# MCU.net
KiCad netlist of a schematic drawn in Altium Designer
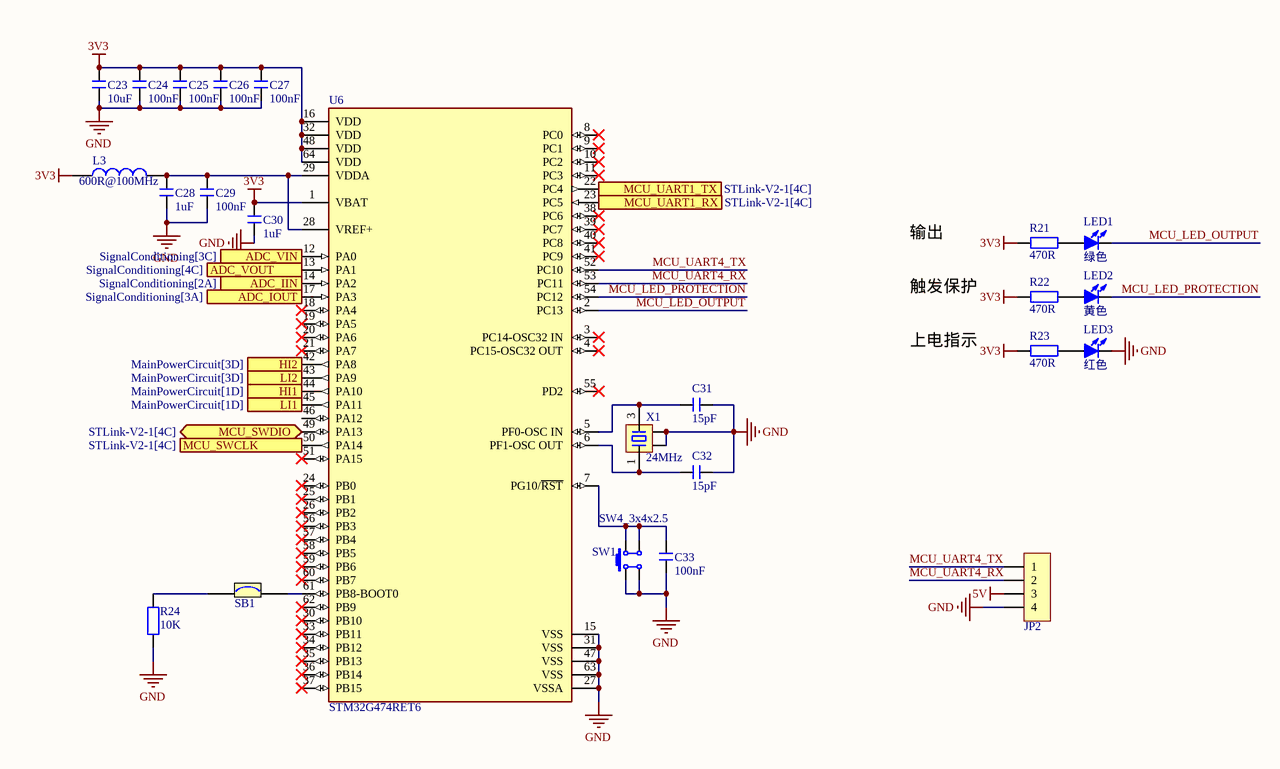
[diagram p0: MCU.SchDoc]

(export (version "E")
  (design (tool "Eeschema 10.0.6"))
  (components
    (comp (ref "C23")
      (value "10uF")
      (footprint "C 0402_L")
      (description "无极性贴片电容")
      (fields (field (name "版权归属") "源创客"))
      (libsource (lib "源创客") (part "C"))
    )
    (comp (ref "C24")
      (value "100nF")
      (footprint "C 0402_L")
      (description "无极性贴片电容")
      (fields (field (name "版权归属") "源创客"))
      (libsource (lib "源创客") (part "C"))
    )
    (comp (ref "C25")
      (value "100nF")
      (footprint "C 0402_L")
      (description "无极性贴片电容")
      (fields (field (name "版权归属") "源创客"))
      (libsource (lib "源创客") (part "C"))
    )
    (comp (ref "C26")
      (value "100nF")
      (footprint "C 0402_L")
      (description "无极性贴片电容")
      (fields (field (name "版权归属") "源创客"))
      (libsource (lib "源创客") (part "C"))
    )
    (comp (ref "C27")
      (value "100nF")
      (footprint "C 0402_L")
      (description "无极性贴片电容")
      (fields (field (name "版权归属") "源创客"))
      (libsource (lib "源创客") (part "C"))
    )
    (comp (ref "C28")
      (value "1uF")
      (footprint "C 0402_L")
      (description "无极性贴片电容")
      (fields (field (name "版权归属") "源创客"))
      (libsource (lib "源创客") (part "C"))
    )
    (comp (ref "C29")
      (value "100nF")
      (footprint "C 0402_L")
      (description "无极性贴片电容")
      (fields (field (name "版权归属") "源创客"))
      (libsource (lib "源创客") (part "C"))
    )
    (comp (ref "C30")
      (value "1uF")
      (footprint "C 0402_L")
      (description "无极性贴片电容")
      (fields (field (name "版权归属") "源创客"))
      (libsource (lib "源创客") (part "C"))
    )
    (comp (ref "C31")
      (value "15pF")
      (footprint "C 0402_L")
      (description "无极性贴片电容")
      (fields (field (name "版权归属") "源创客"))
      (libsource (lib "源创客") (part "C"))
    )
    (comp (ref "C32")
      (value "15pF")
      (footprint "C 0402_L")
      (description "无极性贴片电容")
      (fields (field (name "版权归属") "源创客"))
      (libsource (lib "源创客") (part "C"))
    )
    (comp (ref "C33")
      (value "100nF")
      (footprint "C 0402_L")
      (description "无极性贴片电容")
      (fields (field (name "版权归属") "源创客"))
      (libsource (lib "源创客") (part "C"))
    )
    (comp (ref "JP2")
      (value "HDR-1X4")
      (footprint "XH2.54-WI-4P")
      (description "4P接插件")
      (libsource (lib "5.5 - 2.54mm(100mil)连接器(XH2.54)") (part "Header 4"))
    )
    (comp (ref "L3")
      (value "600R@100MHz")
      (footprint "L 0603")
      (description "小功率贴片电感")
      (fields (field (name "版权归属") "源创客"))
      (libsource (lib "源创客") (part "L"))
    )
    (comp (ref "LED1")
      (value "绿色")
      (footprint "LED 0603G")
      (description "贴片LED")
      (fields (field (name "版权归属") "源创客"))
      (libsource (lib "源创客") (part "LED-SMD"))
    )
    (comp (ref "LED2")
      (value "黄色")
      (footprint "LED 0603Y")
      (description "贴片LED")
      (fields (field (name "版权归属") "源创客"))
      (libsource (lib "源创客") (part "LED-SMD"))
    )
    (comp (ref "LED3")
      (value "红色")
      (footprint "LED 0603R")
      (description "贴片LED")
      (fields (field (name "版权归属") "源创客"))
      (libsource (lib "源创客") (part "LED-SMD"))
    )
    (comp (ref "R21")
      (value "470R")
      (footprint "R 0402_L")
      (description "贴片电阻")
      (fields (field (name "版权归属") "源创客"))
      (libsource (lib "源创客") (part "R"))
    )
    (comp (ref "R22")
      (value "470R")
      (footprint "R 0402_L")
      (description "贴片电阻")
      (fields (field (name "版权归属") "源创客"))
      (libsource (lib "源创客") (part "R"))
    )
    (comp (ref "R23")
      (value "470R")
      (footprint "R 0402_L")
      (description "贴片电阻")
      (fields (field (name "版权归属") "源创客"))
      (libsource (lib "源创客") (part "R"))
    )
    (comp (ref "R24")
      (value "10K")
      (footprint "R 0402_L")
      (description "贴片电阻")
      (fields (field (name "版权归属") "源创客"))
      (libsource (lib "源创客") (part "R"))
    )
    (comp (ref "SB1")
      (value "SelectBit")
      (footprint "SelectBit 0402")
      (description "跨接桥，用于选择不同的模式，可以用锡连上，或者焊上0R电阻")
      (libsource (lib "Display") (part "SelectBit"))
    )
    (comp (ref "SW1")
      (value "SW4_3x4x2.5")
      (footprint "SW4_3x4x2.5")
      (libsource (lib "DigitalBuckBoost") (part "SW4_3x4x2.5"))
    )
    (comp (ref "U6")
      (value "STM32G474RET6")
      (footprint "FP-LQFP64-5W-MFG")
      (description "MAINSTREAM ARM CORTEX-M4 CORE WI")
      (fields
        (field (name "MANUFACTURER") "STMicroelectronics")
        (field (name "OCTOPART") "https://octopart.com/stm32g474ret6-stmicroelectronics-102308483")
      )
      (libsource (lib "Altium Content Vault") (part "f7e4c2ab6713028e27effac94efeea5"))
    )
    (comp (ref "X1")
      (value "24MHz")
      (footprint "XTAL-3225-4P")
      (description "4脚无源晶振(谐振器）")
      (libsource (lib "0.1 - 电阻-电容-电感-晶振-晶体-磁珠-电位器") (part "XTAL-4P"))
    )
  )
  (nets
    (net (code "1") (name "/ADC_IIN") (class "Default")
      (node (ref "U6") (pin "14") (pinfunction "PA2_14") (pintype "input"))
    )
    (net (code "2") (name "/ADC_IOUT") (class "Default")
      (node (ref "U6") (pin "17") (pinfunction "PA3_17") (pintype "input"))
    )
    (net (code "3") (name "/ADC_VIN") (class "Default")
      (node (ref "U6") (pin "12") (pinfunction "PA0_12") (pintype "input"))
    )
    (net (code "4") (name "/ADC_VOUT") (class "Default")
      (node (ref "U6") (pin "13") (pinfunction "PA1_13") (pintype "input"))
    )
    (net (code "5") (name "/HI1") (class "Default")
      (node (ref "U6") (pin "44") (pinfunction "PA10_44") (pintype "output"))
    )
    (net (code "6") (name "/HI2") (class "Default")
      (node (ref "U6") (pin "42") (pinfunction "PA8_42") (pintype "output"))
    )
    (net (code "7") (name "/LI1") (class "Default")
      (node (ref "U6") (pin "45") (pinfunction "PA11_45") (pintype "output"))
    )
    (net (code "8") (name "/LI2") (class "Default")
      (node (ref "U6") (pin "43") (pinfunction "PA9_43") (pintype "output"))
    )
    (net (code "9") (name "/MCU_LED_OUTPUT") (class "Default")
      (node (ref "LED1") (pin "2") (pinfunction "K_2") (pintype "passive"))
      (node (ref "U6") (pin "2") (pinfunction "PC13_2") (pintype "bidirectional"))
    )
    (net (code "10") (name "/MCU_LED_PROTECTION") (class "Default")
      (node (ref "LED2") (pin "2") (pinfunction "K_2") (pintype "passive"))
      (node (ref "U6") (pin "54") (pinfunction "PC12_54") (pintype "bidirectional"))
    )
    (net (code "11") (name "/MCU_SWCLK") (class "Default")
      (node (ref "U6") (pin "50") (pinfunction "PA14_50") (pintype "output"))
    )
    (net (code "12") (name "/MCU_SWDIO") (class "Default")
      (node (ref "U6") (pin "49") (pinfunction "PA13_49") (pintype "bidirectional"))
    )
    (net (code "13") (name "/MCU_UART1_RX") (class "Default")
      (node (ref "U6") (pin "23") (pinfunction "PC5_23") (pintype "input"))
    )
    (net (code "14") (name "/MCU_UART1_TX") (class "Default")
      (node (ref "U6") (pin "22") (pinfunction "PC4_22") (pintype "output"))
    )
    (net (code "15") (name "/MCU_UART4_RX") (class "Default")
      (node (ref "JP2") (pin "2") (pinfunction "2_2") (pintype "passive"))
      (node (ref "U6") (pin "53") (pinfunction "PC11_53") (pintype "bidirectional"))
    )
    (net (code "16") (name "/MCU_UART4_TX") (class "Default")
      (node (ref "JP2") (pin "1") (pinfunction "1_1") (pintype "passive"))
      (node (ref "U6") (pin "52") (pinfunction "PC10_52") (pintype "bidirectional"))
    )
    (net (code "17") (name "3V3") (class "Default")
      (node (ref "C23") (pin "2") (pinfunction "2_2") (pintype "passive"))
      (node (ref "C24") (pin "2") (pinfunction "2_2") (pintype "passive"))
      (node (ref "C25") (pin "2") (pinfunction "2_2") (pintype "passive"))
      (node (ref "C26") (pin "2") (pinfunction "2_2") (pintype "passive"))
      (node (ref "C27") (pin "2") (pinfunction "2_2") (pintype "passive"))
      (node (ref "C30") (pin "2") (pinfunction "2_2") (pintype "passive"))
      (node (ref "L3") (pin "1") (pinfunction "1_1") (pintype "passive"))
      (node (ref "R21") (pin "2") (pinfunction "2_2") (pintype "passive"))
      (node (ref "R22") (pin "2") (pinfunction "2_2") (pintype "passive"))
      (node (ref "R23") (pin "2") (pinfunction "2_2") (pintype "passive"))
      (node (ref "U6") (pin "1") (pinfunction "VBAT_1") (pintype "power_in"))
      (node (ref "U6") (pin "16") (pinfunction "VDD_16") (pintype "power_in"))
      (node (ref "U6") (pin "32") (pinfunction "VDD_32") (pintype "power_in"))
      (node (ref "U6") (pin "48") (pinfunction "VDD_48") (pintype "power_in"))
      (node (ref "U6") (pin "64") (pinfunction "VDD_64") (pintype "power_in"))
    )
    (net (code "18") (name "5V") (class "Default")
      (node (ref "JP2") (pin "3") (pinfunction "3_3") (pintype "passive"))
    )
    (net (code "19") (name "GND") (class "Default")
      (node (ref "C23") (pin "1") (pinfunction "1_1") (pintype "passive"))
      (node (ref "C24") (pin "1") (pinfunction "1_1") (pintype "passive"))
      (node (ref "C25") (pin "1") (pinfunction "1_1") (pintype "passive"))
      (node (ref "C26") (pin "1") (pinfunction "1_1") (pintype "passive"))
      (node (ref "C27") (pin "1") (pinfunction "1_1") (pintype "passive"))
      (node (ref "C28") (pin "1") (pinfunction "1_1") (pintype "passive"))
      (node (ref "C29") (pin "1") (pinfunction "1_1") (pintype "passive"))
      (node (ref "C30") (pin "1") (pinfunction "1_1") (pintype "passive"))
      (node (ref "C31") (pin "1") (pinfunction "1_1") (pintype "passive"))
      (node (ref "C32") (pin "1") (pinfunction "1_1") (pintype "passive"))
      (node (ref "C33") (pin "2") (pinfunction "2_2") (pintype "passive"))
      (node (ref "JP2") (pin "4") (pinfunction "4_4") (pintype "passive"))
      (node (ref "LED3") (pin "2") (pinfunction "K_2") (pintype "passive"))
      (node (ref "R24") (pin "2") (pinfunction "2_2") (pintype "passive"))
      (node (ref "SW1") (pin "1") (pinfunction "1_1") (pintype "passive"))
      (node (ref "SW1") (pin "2") (pinfunction "2_2") (pintype "passive"))
      (node (ref "U6") (pin "15") (pinfunction "VSS_15") (pintype "power_in"))
      (node (ref "U6") (pin "27") (pinfunction "VSSA_27") (pintype "power_in"))
      (node (ref "U6") (pin "31") (pinfunction "VSS_31") (pintype "power_in"))
      (node (ref "U6") (pin "47") (pinfunction "VSS_47") (pintype "power_in"))
      (node (ref "U6") (pin "63") (pinfunction "VSS_63") (pintype "power_in"))
      (node (ref "X1") (pin "2") (pinfunction "2_2") (pintype "passive"))
      (node (ref "X1") (pin "4") (pinfunction "4_4") (pintype "passive"))
    )
    (net (code "20") (name "Net-(LED1-A)") (class "Default")
      (node (ref "LED1") (pin "1") (pinfunction "A_1") (pintype "passive"))
      (node (ref "R21") (pin "1") (pinfunction "1_1") (pintype "passive"))
    )
    (net (code "21") (name "Net-(LED2-A)") (class "Default")
      (node (ref "LED2") (pin "1") (pinfunction "A_1") (pintype "passive"))
      (node (ref "R22") (pin "1") (pinfunction "1_1") (pintype "passive"))
    )
    (net (code "22") (name "Net-(LED3-A)") (class "Default")
      (node (ref "LED3") (pin "1") (pinfunction "A_1") (pintype "passive"))
      (node (ref "R23") (pin "1") (pinfunction "1_1") (pintype "passive"))
    )
    (net (code "23") (name "Net-(R24-Pad1)") (class "Default")
      (node (ref "R24") (pin "1") (pinfunction "1_1") (pintype "passive"))
      (node (ref "SB1") (pin "1") (pinfunction "1_1") (pintype "passive"))
    )
    (net (code "24") (name "Net-(U6-PB8-BOOT0)") (class "Default")
      (node (ref "SB1") (pin "2") (pinfunction "2_2") (pintype "passive"))
      (node (ref "U6") (pin "61") (pinfunction "PB8-BOOT0_61") (pintype "bidirectional"))
    )
    (net (code "25") (name "Net-(U6-PF0-OSC_IN)") (class "Default")
      (node (ref "C31") (pin "2") (pinfunction "2_2") (pintype "passive"))
      (node (ref "U6") (pin "5") (pinfunction "PF0-OSC_IN_5") (pintype "bidirectional"))
      (node (ref "X1") (pin "3") (pinfunction "3_3") (pintype "passive"))
    )
    (net (code "26") (name "Net-(U6-PF1-OSC_OUT)") (class "Default")
      (node (ref "C32") (pin "2") (pinfunction "2_2") (pintype "passive"))
      (node (ref "U6") (pin "6") (pinfunction "PF1-OSC_OUT_6") (pintype "bidirectional"))
      (node (ref "X1") (pin "1") (pinfunction "1_1") (pintype "passive"))
    )
    (net (code "27") (name "Net-(U6-PG10{slash}~{RST})") (class "Default")
      (node (ref "C33") (pin "1") (pinfunction "1_1") (pintype "passive"))
      (node (ref "SW1") (pin "3") (pinfunction "3_3") (pintype "passive"))
      (node (ref "SW1") (pin "4") (pinfunction "4_4") (pintype "passive"))
      (node (ref "U6") (pin "7") (pinfunction "PG10/~{RST}_7") (pintype "bidirectional"))
    )
    (net (code "28") (name "Net-(U6-VDDA)") (class "Default")
      (node (ref "C28") (pin "2") (pinfunction "2_2") (pintype "passive"))
      (node (ref "C29") (pin "2") (pinfunction "2_2") (pintype "passive"))
      (node (ref "L3") (pin "2") (pinfunction "2_2") (pintype "passive"))
      (node (ref "U6") (pin "28") (pinfunction "VREF+_28") (pintype "power_in"))
      (node (ref "U6") (pin "29") (pinfunction "VDDA_29") (pintype "power_in"))
    )
    (net (code "29") (name "unconnected-(U6-PA4-Pad18)") (class "Default")
      (node (ref "U6") (pin "18") (pinfunction "PA4_18") (pintype "bidirectional+no_connect"))
    )
    (net (code "30") (name "unconnected-(U6-PA5-Pad19)") (class "Default")
      (node (ref "U6") (pin "19") (pinfunction "PA5_19") (pintype "bidirectional+no_connect"))
    )
    (net (code "31") (name "unconnected-(U6-PA6-Pad20)") (class "Default")
      (node (ref "U6") (pin "20") (pinfunction "PA6_20") (pintype "bidirectional+no_connect"))
    )
    (net (code "32") (name "unconnected-(U6-PA7-Pad21)") (class "Default")
      (node (ref "U6") (pin "21") (pinfunction "PA7_21") (pintype "bidirectional+no_connect"))
    )
    (net (code "33") (name "unconnected-(U6-PA12-Pad46)") (class "Default")
      (node (ref "U6") (pin "46") (pinfunction "PA12_46") (pintype "bidirectional"))
    )
    (net (code "34") (name "unconnected-(U6-PA15-Pad51)") (class "Default")
      (node (ref "U6") (pin "51") (pinfunction "PA15_51") (pintype "bidirectional+no_connect"))
    )
    (net (code "35") (name "unconnected-(U6-PB0-Pad24)") (class "Default")
      (node (ref "U6") (pin "24") (pinfunction "PB0_24") (pintype "bidirectional+no_connect"))
    )
    (net (code "36") (name "unconnected-(U6-PB1-Pad25)") (class "Default")
      (node (ref "U6") (pin "25") (pinfunction "PB1_25") (pintype "bidirectional+no_connect"))
    )
    (net (code "37") (name "unconnected-(U6-PB2-Pad26)") (class "Default")
      (node (ref "U6") (pin "26") (pinfunction "PB2_26") (pintype "bidirectional+no_connect"))
    )
    (net (code "38") (name "unconnected-(U6-PB3-Pad56)") (class "Default")
      (node (ref "U6") (pin "56") (pinfunction "PB3_56") (pintype "bidirectional+no_connect"))
    )
    (net (code "39") (name "unconnected-(U6-PB4-Pad57)") (class "Default")
      (node (ref "U6") (pin "57") (pinfunction "PB4_57") (pintype "bidirectional+no_connect"))
    )
    (net (code "40") (name "unconnected-(U6-PB5-Pad58)") (class "Default")
      (node (ref "U6") (pin "58") (pinfunction "PB5_58") (pintype "bidirectional+no_connect"))
    )
    (net (code "41") (name "unconnected-(U6-PB6-Pad59)") (class "Default")
      (node (ref "U6") (pin "59") (pinfunction "PB6_59") (pintype "bidirectional+no_connect"))
    )
    (net (code "42") (name "unconnected-(U6-PB7-Pad60)") (class "Default")
      (node (ref "U6") (pin "60") (pinfunction "PB7_60") (pintype "bidirectional+no_connect"))
    )
    (net (code "43") (name "unconnected-(U6-PB9-Pad62)") (class "Default")
      (node (ref "U6") (pin "62") (pinfunction "PB9_62") (pintype "bidirectional+no_connect"))
    )
    (net (code "44") (name "unconnected-(U6-PB10-Pad30)") (class "Default")
      (node (ref "U6") (pin "30") (pinfunction "PB10_30") (pintype "bidirectional+no_connect"))
    )
    (net (code "45") (name "unconnected-(U6-PB11-Pad33)") (class "Default")
      (node (ref "U6") (pin "33") (pinfunction "PB11_33") (pintype "bidirectional+no_connect"))
    )
    (net (code "46") (name "unconnected-(U6-PB12-Pad34)") (class "Default")
      (node (ref "U6") (pin "34") (pinfunction "PB12_34") (pintype "bidirectional+no_connect"))
    )
    (net (code "47") (name "unconnected-(U6-PB13-Pad35)") (class "Default")
      (node (ref "U6") (pin "35") (pinfunction "PB13_35") (pintype "bidirectional+no_connect"))
    )
    (net (code "48") (name "unconnected-(U6-PB14-Pad36)") (class "Default")
      (node (ref "U6") (pin "36") (pinfunction "PB14_36") (pintype "bidirectional+no_connect"))
    )
    (net (code "49") (name "unconnected-(U6-PB15-Pad37)") (class "Default")
      (node (ref "U6") (pin "37") (pinfunction "PB15_37") (pintype "bidirectional+no_connect"))
    )
    (net (code "50") (name "unconnected-(U6-PC0-Pad8)") (class "Default")
      (node (ref "U6") (pin "8") (pinfunction "PC0_8") (pintype "bidirectional+no_connect"))
    )
    (net (code "51") (name "unconnected-(U6-PC1-Pad9)") (class "Default")
      (node (ref "U6") (pin "9") (pinfunction "PC1_9") (pintype "bidirectional+no_connect"))
    )
    (net (code "52") (name "unconnected-(U6-PC2-Pad10)") (class "Default")
      (node (ref "U6") (pin "10") (pinfunction "PC2_10") (pintype "bidirectional+no_connect"))
    )
    (net (code "53") (name "unconnected-(U6-PC3-Pad11)") (class "Default")
      (node (ref "U6") (pin "11") (pinfunction "PC3_11") (pintype "bidirectional+no_connect"))
    )
    (net (code "54") (name "unconnected-(U6-PC6-Pad38)") (class "Default")
      (node (ref "U6") (pin "38") (pinfunction "PC6_38") (pintype "bidirectional+no_connect"))
    )
    (net (code "55") (name "unconnected-(U6-PC7-Pad39)") (class "Default")
      (node (ref "U6") (pin "39") (pinfunction "PC7_39") (pintype "bidirectional+no_connect"))
    )
    (net (code "56") (name "unconnected-(U6-PC8-Pad40)") (class "Default")
      (node (ref "U6") (pin "40") (pinfunction "PC8_40") (pintype "bidirectional+no_connect"))
    )
    (net (code "57") (name "unconnected-(U6-PC9-Pad41)") (class "Default")
      (node (ref "U6") (pin "41") (pinfunction "PC9_41") (pintype "bidirectional+no_connect"))
    )
    (net (code "58") (name "unconnected-(U6-PC14-OSC32_IN-Pad3)") (class "Default")
      (node (ref "U6") (pin "3") (pinfunction "PC14-OSC32_IN_3") (pintype "bidirectional+no_connect"))
    )
    (net (code "59") (name "unconnected-(U6-PC15-OSC32_OUT-Pad4)") (class "Default")
      (node (ref "U6") (pin "4") (pinfunction "PC15-OSC32_OUT_4") (pintype "bidirectional+no_connect"))
    )
    (net (code "60") (name "unconnected-(U6-PD2-Pad55)") (class "Default")
      (node (ref "U6") (pin "55") (pinfunction "PD2_55") (pintype "bidirectional+no_connect"))
    )
  )
)
